# 03-CORE_BOARD.net
KiCad netlist of a schematic drawn in Altium Designer
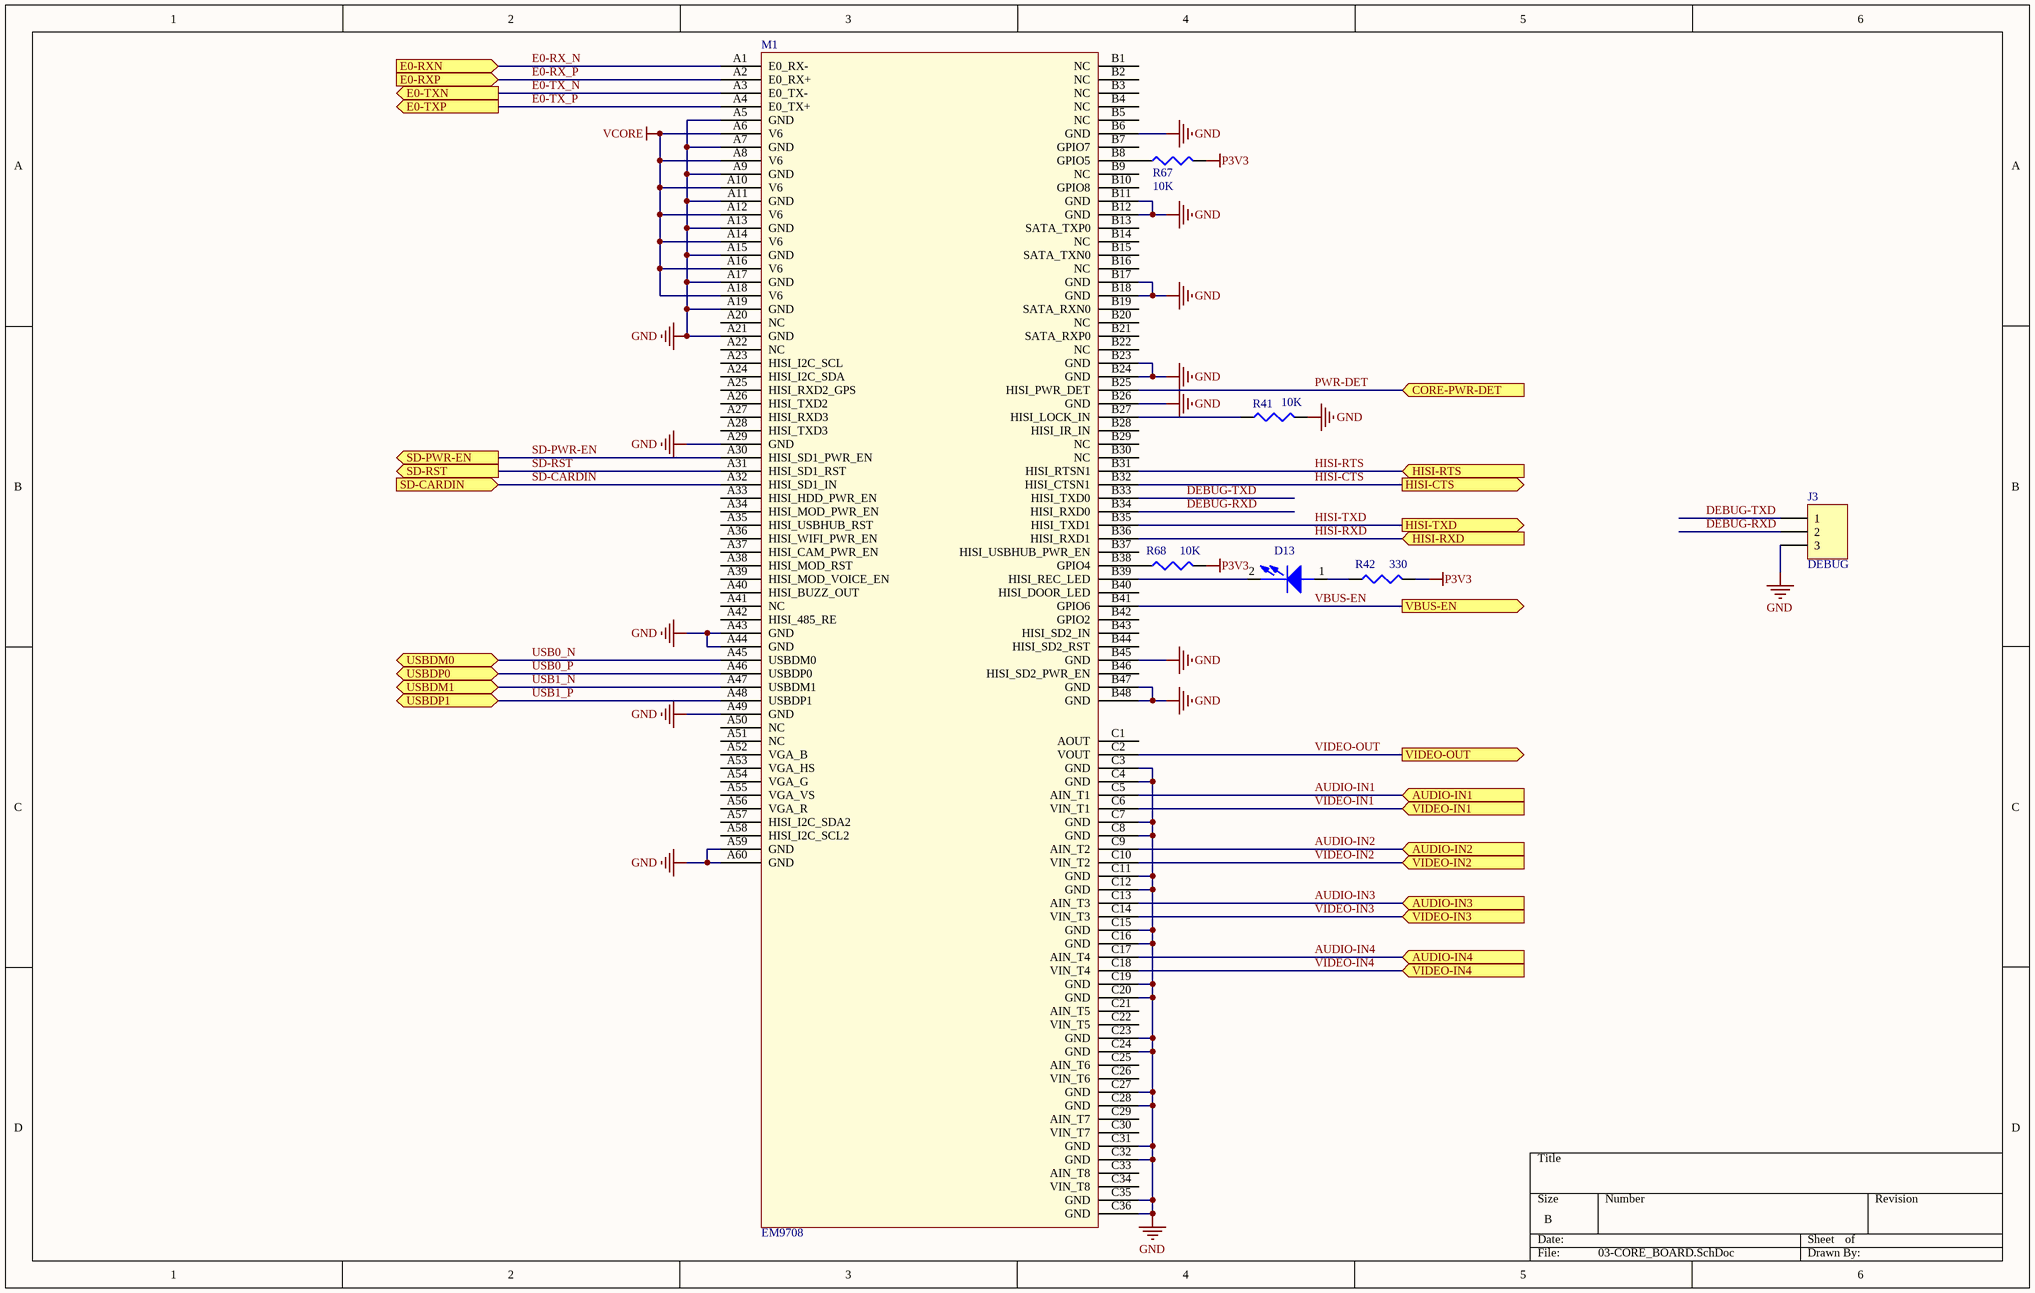
[diagram p0: 03-CORE_BOARD.SchDoc]

(export (version "E")
  (design (tool "Eeschema 10.0.6"))
  (components
    (comp (ref "D13") (value "LED GREEN") (footprint "LED0603") (libsource (lib "*") (part "LN01401_1")))
    (comp (ref "J3")
      (value "DEBUG")
      (footprint "HDR1X3")
      (description "Header, 3-Pin")
      (fields (field (name "PUBLISHER") "Altium Limited"))
      (libsource (lib "Miscellaneous Connectors") (part "Header 3"))
    )
    (comp (ref "M1") (value "EM9708") (footprint "EM9708") (libsource (lib "Schlib") (part "EM9708")))
    (comp (ref "R41")
      (value "10K")
      (footprint "0402")
      (description "Resistor")
      (fields (field (name "PUBLISHER") "Altium Limited"))
      (libsource (lib "Miscellaneous Devices") (part "Res3"))
    )
    (comp (ref "R42") (value "330") (footprint "0402") (libsource (lib "*") (part "CR16-1003FM")))
    (comp (ref "R67")
      (value "10K")
      (footprint "0402")
      (description "Resistor")
      (fields (field (name "PUBLISHER") "Altium Limited"))
      (libsource (lib "Miscellaneous Devices") (part "Res3"))
    )
    (comp (ref "R68")
      (value "10K")
      (footprint "0402")
      (description "Resistor")
      (fields (field (name "PUBLISHER") "Altium Limited"))
      (libsource (lib "Miscellaneous Devices") (part "Res3"))
    )
  )
  (nets
    (net (code "1") (name "/AUDIO-IN1") (class "Default")
      (node (ref "M1") (pin "C5") (pinfunction "AIN_T1_C5") (pintype "passive"))
    )
    (net (code "2") (name "/AUDIO-IN2") (class "Default")
      (node (ref "M1") (pin "C9") (pinfunction "AIN_T2_C9") (pintype "passive"))
    )
    (net (code "3") (name "/AUDIO-IN3") (class "Default")
      (node (ref "M1") (pin "C13") (pinfunction "AIN_T3_C13") (pintype "passive"))
    )
    (net (code "4") (name "/AUDIO-IN4") (class "Default")
      (node (ref "M1") (pin "C17") (pinfunction "AIN_T4_C17") (pintype "passive"))
    )
    (net (code "5") (name "/DEBUG-RXD") (class "Default")
      (node (ref "J3") (pin "2") (pinfunction "2_2") (pintype "passive"))
      (node (ref "M1") (pin "B34") (pinfunction "HISI_RXD0_B34") (pintype "passive"))
    )
    (net (code "6") (name "/DEBUG-TXD") (class "Default")
      (node (ref "J3") (pin "1") (pinfunction "1_1") (pintype "passive"))
      (node (ref "M1") (pin "B33") (pinfunction "HISI_TXD0_B33") (pintype "passive"))
    )
    (net (code "7") (name "/E0-RX_N") (class "Default")
      (node (ref "M1") (pin "A1") (pinfunction "E0_RX-_A1") (pintype "passive"))
    )
    (net (code "8") (name "/E0-RX_P") (class "Default")
      (node (ref "M1") (pin "A2") (pinfunction "E0_RX+_A2") (pintype "passive"))
    )
    (net (code "9") (name "/E0-TX_N") (class "Default")
      (node (ref "M1") (pin "A3") (pinfunction "E0_TX-_A3") (pintype "passive"))
    )
    (net (code "10") (name "/E0-TX_P") (class "Default")
      (node (ref "M1") (pin "A4") (pinfunction "E0_TX+_A4") (pintype "passive"))
    )
    (net (code "11") (name "/HISI-CTS") (class "Default")
      (node (ref "M1") (pin "B32") (pinfunction "HISI_CTSN1_B32") (pintype "passive"))
    )
    (net (code "12") (name "/HISI-RTS") (class "Default")
      (node (ref "M1") (pin "B31") (pinfunction "HISI_RTSN1_B31") (pintype "passive"))
    )
    (net (code "13") (name "/HISI-RXD") (class "Default")
      (node (ref "M1") (pin "B36") (pinfunction "HISI_RXD1_B36") (pintype "passive"))
    )
    (net (code "14") (name "/HISI-TXD") (class "Default")
      (node (ref "M1") (pin "B35") (pinfunction "HISI_TXD1_B35") (pintype "passive"))
    )
    (net (code "15") (name "/PWR-DET") (class "Default")
      (node (ref "M1") (pin "B25") (pinfunction "HISI_PWR_DET_B25") (pintype "passive"))
    )
    (net (code "16") (name "/SD-CARDIN") (class "Default")
      (node (ref "M1") (pin "A32") (pinfunction "HISI_SD1_IN_A32") (pintype "passive"))
    )
    (net (code "17") (name "/SD-PWR-EN") (class "Default")
      (node (ref "M1") (pin "A30") (pinfunction "HISI_SD1_PWR_EN_A30") (pintype "passive"))
    )
    (net (code "18") (name "/SD-RST") (class "Default")
      (node (ref "M1") (pin "A31") (pinfunction "HISI_SD1_RST_A31") (pintype "passive"))
    )
    (net (code "19") (name "/USB0_N") (class "Default")
      (node (ref "M1") (pin "A45") (pinfunction "USBDM0_A45") (pintype "passive"))
    )
    (net (code "20") (name "/USB0_P") (class "Default")
      (node (ref "M1") (pin "A46") (pinfunction "USBDP0_A46") (pintype "passive"))
    )
    (net (code "21") (name "/USB1_N") (class "Default")
      (node (ref "M1") (pin "A47") (pinfunction "USBDM1_A47") (pintype "passive"))
    )
    (net (code "22") (name "/USB1_P") (class "Default")
      (node (ref "M1") (pin "A48") (pinfunction "USBDP1_A48") (pintype "passive"))
    )
    (net (code "23") (name "/VBUS-EN") (class "Default")
      (node (ref "M1") (pin "B41") (pinfunction "GPIO6_B41") (pintype "passive"))
    )
    (net (code "24") (name "/VIDEO-IN1") (class "Default")
      (node (ref "M1") (pin "C6") (pinfunction "VIN_T1_C6") (pintype "passive"))
    )
    (net (code "25") (name "/VIDEO-IN2") (class "Default")
      (node (ref "M1") (pin "C10") (pinfunction "VIN_T2_C10") (pintype "passive"))
    )
    (net (code "26") (name "/VIDEO-IN3") (class "Default")
      (node (ref "M1") (pin "C14") (pinfunction "VIN_T3_C14") (pintype "passive"))
    )
    (net (code "27") (name "/VIDEO-IN4") (class "Default")
      (node (ref "M1") (pin "C18") (pinfunction "VIN_T4_C18") (pintype "passive"))
    )
    (net (code "28") (name "/VIDEO-OUT") (class "Default")
      (node (ref "M1") (pin "C2") (pinfunction "VOUT_C2") (pintype "passive"))
    )
    (net (code "29") (name "GND") (class "Default")
      (node (ref "J3") (pin "3") (pinfunction "3_3") (pintype "passive"))
      (node (ref "M1") (pin "A11") (pinfunction "GND_A11") (pintype "passive"))
      (node (ref "M1") (pin "A13") (pinfunction "GND_A13") (pintype "passive"))
      (node (ref "M1") (pin "A15") (pinfunction "GND_A15") (pintype "passive"))
      (node (ref "M1") (pin "A17") (pinfunction "GND_A17") (pintype "passive"))
      (node (ref "M1") (pin "A19") (pinfunction "GND_A19") (pintype "passive"))
      (node (ref "M1") (pin "A21") (pinfunction "GND_A21") (pintype "passive"))
      (node (ref "M1") (pin "A29") (pinfunction "GND_A29") (pintype "passive"))
      (node (ref "M1") (pin "A43") (pinfunction "GND_A43") (pintype "passive"))
      (node (ref "M1") (pin "A44") (pinfunction "GND_A44") (pintype "passive"))
      (node (ref "M1") (pin "A49") (pinfunction "GND_A49") (pintype "passive"))
      (node (ref "M1") (pin "A5") (pinfunction "GND_A5") (pintype "passive"))
      (node (ref "M1") (pin "A59") (pinfunction "GND_A59") (pintype "passive"))
      (node (ref "M1") (pin "A60") (pinfunction "GND_A60") (pintype "passive"))
      (node (ref "M1") (pin "A7") (pinfunction "GND_A7") (pintype "passive"))
      (node (ref "M1") (pin "A9") (pinfunction "GND_A9") (pintype "passive"))
      (node (ref "M1") (pin "B11") (pinfunction "GND_B11") (pintype "passive"))
      (node (ref "M1") (pin "B12") (pinfunction "GND_B12") (pintype "passive"))
      (node (ref "M1") (pin "B17") (pinfunction "GND_B17") (pintype "passive"))
      (node (ref "M1") (pin "B18") (pinfunction "GND_B18") (pintype "passive"))
      (node (ref "M1") (pin "B23") (pinfunction "GND_B23") (pintype "passive"))
      (node (ref "M1") (pin "B24") (pinfunction "GND_B24") (pintype "passive"))
      (node (ref "M1") (pin "B26") (pinfunction "GND_B26") (pintype "passive"))
      (node (ref "M1") (pin "B45") (pinfunction "GND_B45") (pintype "passive"))
      (node (ref "M1") (pin "B47") (pinfunction "GND_B47") (pintype "passive"))
      (node (ref "M1") (pin "B48") (pinfunction "GND_B48") (pintype "passive"))
      (node (ref "M1") (pin "B6") (pinfunction "GND_B6") (pintype "passive"))
      (node (ref "M1") (pin "C11") (pinfunction "GND_C11") (pintype "passive"))
      (node (ref "M1") (pin "C12") (pinfunction "GND_C12") (pintype "passive"))
      (node (ref "M1") (pin "C15") (pinfunction "GND_C15") (pintype "passive"))
      (node (ref "M1") (pin "C16") (pinfunction "GND_C16") (pintype "passive"))
      (node (ref "M1") (pin "C19") (pinfunction "GND_C19") (pintype "passive"))
      (node (ref "M1") (pin "C20") (pinfunction "GND_C20") (pintype "passive"))
      (node (ref "M1") (pin "C23") (pinfunction "GND_C23") (pintype "passive"))
      (node (ref "M1") (pin "C24") (pinfunction "GND_C24") (pintype "passive"))
      (node (ref "M1") (pin "C27") (pinfunction "GND_C27") (pintype "passive"))
      (node (ref "M1") (pin "C28") (pinfunction "GND_C28") (pintype "passive"))
      (node (ref "M1") (pin "C3") (pinfunction "GND_C3") (pintype "passive"))
      (node (ref "M1") (pin "C31") (pinfunction "GND_C31") (pintype "passive"))
      (node (ref "M1") (pin "C32") (pinfunction "GND_C32") (pintype "passive"))
      (node (ref "M1") (pin "C35") (pinfunction "GND_C35") (pintype "passive"))
      (node (ref "M1") (pin "C36") (pinfunction "GND_C36") (pintype "passive"))
      (node (ref "M1") (pin "C4") (pinfunction "GND_C4") (pintype "passive"))
      (node (ref "M1") (pin "C7") (pinfunction "GND_C7") (pintype "passive"))
      (node (ref "M1") (pin "C8") (pinfunction "GND_C8") (pintype "passive"))
      (node (ref "R41") (pin "2") (pinfunction "2_2") (pintype "passive"))
    )
    (net (code "30") (name "Net-(D13-ANODE)") (class "Default")
      (node (ref "D13") (pin "1") (pinfunction "ANODE_1") (pintype "passive"))
      (node (ref "R42") (pin "2") (pinfunction "2_2") (pintype "passive"))
    )
    (net (code "31") (name "Net-(D13-CATHODE)") (class "Default")
      (node (ref "D13") (pin "2") (pinfunction "CATHODE_2") (pintype "passive"))
      (node (ref "M1") (pin "B39") (pinfunction "HISI_REC_LED_B39") (pintype "passive"))
    )
    (net (code "32") (name "Net-(M1-GPIO4)") (class "Default")
      (node (ref "M1") (pin "B38") (pinfunction "GPIO4_B38") (pintype "passive"))
      (node (ref "R68") (pin "1") (pinfunction "1_1") (pintype "passive"))
    )
    (net (code "33") (name "Net-(M1-GPIO5)") (class "Default")
      (node (ref "M1") (pin "B8") (pinfunction "GPIO5_B8") (pintype "passive"))
      (node (ref "R67") (pin "1") (pinfunction "1_1") (pintype "passive"))
    )
    (net (code "34") (name "Net-(M1-HISI_LOCK_IN)") (class "Default")
      (node (ref "M1") (pin "B27") (pinfunction "HISI_LOCK_IN_B27") (pintype "passive"))
      (node (ref "R41") (pin "1") (pinfunction "1_1") (pintype "passive"))
    )
    (net (code "35") (name "P3V3") (class "Default")
      (node (ref "R42") (pin "1") (pinfunction "1_1") (pintype "passive"))
      (node (ref "R67") (pin "2") (pinfunction "2_2") (pintype "passive"))
      (node (ref "R68") (pin "2") (pinfunction "2_2") (pintype "passive"))
    )
    (net (code "36") (name "VCORE") (class "Default")
      (node (ref "M1") (pin "A10") (pinfunction "V6_A10") (pintype "passive"))
      (node (ref "M1") (pin "A12") (pinfunction "V6_A12") (pintype "passive"))
      (node (ref "M1") (pin "A14") (pinfunction "V6_A14") (pintype "passive"))
      (node (ref "M1") (pin "A16") (pinfunction "V6_A16") (pintype "passive"))
      (node (ref "M1") (pin "A18") (pinfunction "V6_A18") (pintype "passive"))
      (node (ref "M1") (pin "A6") (pinfunction "V6_A6") (pintype "passive"))
      (node (ref "M1") (pin "A8") (pinfunction "V6_A8") (pintype "passive"))
    )
    (net (code "37") (name "unconnected-(M1-AIN_T5-PadC21)") (class "Default")
      (node (ref "M1") (pin "C21") (pinfunction "AIN_T5_C21") (pintype "passive"))
    )
    (net (code "38") (name "unconnected-(M1-AIN_T6-PadC25)") (class "Default")
      (node (ref "M1") (pin "C25") (pinfunction "AIN_T6_C25") (pintype "passive"))
    )
    (net (code "39") (name "unconnected-(M1-AIN_T7-PadC29)") (class "Default")
      (node (ref "M1") (pin "C29") (pinfunction "AIN_T7_C29") (pintype "passive"))
    )
    (net (code "40") (name "unconnected-(M1-AIN_T8-PadC33)") (class "Default")
      (node (ref "M1") (pin "C33") (pinfunction "AIN_T8_C33") (pintype "passive"))
    )
    (net (code "41") (name "unconnected-(M1-AOUT-PadC1)") (class "Default")
      (node (ref "M1") (pin "C1") (pinfunction "AOUT_C1") (pintype "passive"))
    )
    (net (code "42") (name "unconnected-(M1-GPIO2-PadB42)") (class "Default")
      (node (ref "M1") (pin "B42") (pinfunction "GPIO2_B42") (pintype "passive"))
    )
    (net (code "43") (name "unconnected-(M1-GPIO7-PadB7)") (class "Default")
      (node (ref "M1") (pin "B7") (pinfunction "GPIO7_B7") (pintype "passive"))
    )
    (net (code "44") (name "unconnected-(M1-GPIO8-PadB10)") (class "Default")
      (node (ref "M1") (pin "B10") (pinfunction "GPIO8_B10") (pintype "passive"))
    )
    (net (code "45") (name "unconnected-(M1-HISI_485_RE-PadA42)") (class "Default")
      (node (ref "M1") (pin "A42") (pinfunction "HISI_485_RE_A42") (pintype "passive"))
    )
    (net (code "46") (name "unconnected-(M1-HISI_BUZZ_OUT-PadA40)") (class "Default")
      (node (ref "M1") (pin "A40") (pinfunction "HISI_BUZZ_OUT_A40") (pintype "passive"))
    )
    (net (code "47") (name "unconnected-(M1-HISI_CAM_PWR_EN-PadA37)") (class "Default")
      (node (ref "M1") (pin "A37") (pinfunction "HISI_CAM_PWR_EN_A37") (pintype "passive"))
    )
    (net (code "48") (name "unconnected-(M1-HISI_DOOR_LED-PadB40)") (class "Default")
      (node (ref "M1") (pin "B40") (pinfunction "HISI_DOOR_LED_B40") (pintype "passive"))
    )
    (net (code "49") (name "unconnected-(M1-HISI_HDD_PWR_EN-PadA33)") (class "Default")
      (node (ref "M1") (pin "A33") (pinfunction "HISI_HDD_PWR_EN_A33") (pintype "passive"))
    )
    (net (code "50") (name "unconnected-(M1-HISI_I2C_SCL-PadA23)") (class "Default")
      (node (ref "M1") (pin "A23") (pinfunction "HISI_I2C_SCL_A23") (pintype "passive"))
    )
    (net (code "51") (name "unconnected-(M1-HISI_I2C_SCL2-PadA58)") (class "Default")
      (node (ref "M1") (pin "A58") (pinfunction "HISI_I2C_SCL2_A58") (pintype "passive"))
    )
    (net (code "52") (name "unconnected-(M1-HISI_I2C_SDA-PadA24)") (class "Default")
      (node (ref "M1") (pin "A24") (pinfunction "HISI_I2C_SDA_A24") (pintype "passive"))
    )
    (net (code "53") (name "unconnected-(M1-HISI_I2C_SDA2-PadA57)") (class "Default")
      (node (ref "M1") (pin "A57") (pinfunction "HISI_I2C_SDA2_A57") (pintype "passive"))
    )
    (net (code "54") (name "unconnected-(M1-HISI_IR_IN-PadB28)") (class "Default")
      (node (ref "M1") (pin "B28") (pinfunction "HISI_IR_IN_B28") (pintype "passive"))
    )
    (net (code "55") (name "unconnected-(M1-HISI_MOD_PWR_EN-PadA34)") (class "Default")
      (node (ref "M1") (pin "A34") (pinfunction "HISI_MOD_PWR_EN_A34") (pintype "passive"))
    )
    (net (code "56") (name "unconnected-(M1-HISI_MOD_RST-PadA38)") (class "Default")
      (node (ref "M1") (pin "A38") (pinfunction "HISI_MOD_RST_A38") (pintype "passive"))
    )
    (net (code "57") (name "unconnected-(M1-HISI_MOD_VOICE_EN-PadA39)") (class "Default")
      (node (ref "M1") (pin "A39") (pinfunction "HISI_MOD_VOICE_EN_A39") (pintype "passive"))
    )
    (net (code "58") (name "unconnected-(M1-HISI_RXD2_GPS-PadA25)") (class "Default")
      (node (ref "M1") (pin "A25") (pinfunction "HISI_RXD2_GPS_A25") (pintype "passive"))
    )
    (net (code "59") (name "unconnected-(M1-HISI_RXD3-PadA27)") (class "Default")
      (node (ref "M1") (pin "A27") (pinfunction "HISI_RXD3_A27") (pintype "passive"))
    )
    (net (code "60") (name "unconnected-(M1-HISI_SD2_IN-PadB43)") (class "Default")
      (node (ref "M1") (pin "B43") (pinfunction "HISI_SD2_IN_B43") (pintype "passive"))
    )
    (net (code "61") (name "unconnected-(M1-HISI_SD2_PWR_EN-PadB46)") (class "Default")
      (node (ref "M1") (pin "B46") (pinfunction "HISI_SD2_PWR_EN_B46") (pintype "passive"))
    )
    (net (code "62") (name "unconnected-(M1-HISI_SD2_RST-PadB44)") (class "Default")
      (node (ref "M1") (pin "B44") (pinfunction "HISI_SD2_RST_B44") (pintype "passive"))
    )
    (net (code "63") (name "unconnected-(M1-HISI_TXD2-PadA26)") (class "Default")
      (node (ref "M1") (pin "A26") (pinfunction "HISI_TXD2_A26") (pintype "passive"))
    )
    (net (code "64") (name "unconnected-(M1-HISI_TXD3-PadA28)") (class "Default")
      (node (ref "M1") (pin "A28") (pinfunction "HISI_TXD3_A28") (pintype "passive"))
    )
    (net (code "65") (name "unconnected-(M1-HISI_USBHUB_PWR_EN-PadB37)") (class "Default")
      (node (ref "M1") (pin "B37") (pinfunction "HISI_USBHUB_PWR_EN_B37") (pintype "passive"))
    )
    (net (code "66") (name "unconnected-(M1-HISI_USBHUB_RST-PadA35)") (class "Default")
      (node (ref "M1") (pin "A35") (pinfunction "HISI_USBHUB_RST_A35") (pintype "passive"))
    )
    (net (code "67") (name "unconnected-(M1-HISI_WIFI_PWR_EN-PadA36)") (class "Default")
      (node (ref "M1") (pin "A36") (pinfunction "HISI_WIFI_PWR_EN_A36") (pintype "passive"))
    )
    (net (code "68") (name "unconnected-(M1-NC-PadA20)") (class "Default")
      (node (ref "M1") (pin "A20") (pinfunction "NC_A20") (pintype "passive"))
    )
    (net (code "69") (name "unconnected-(M1-NC-PadA22)") (class "Default")
      (node (ref "M1") (pin "A22") (pinfunction "NC_A22") (pintype "passive"))
    )
    (net (code "70") (name "unconnected-(M1-NC-PadA41)") (class "Default")
      (node (ref "M1") (pin "A41") (pinfunction "NC_A41") (pintype "passive"))
    )
    (net (code "71") (name "unconnected-(M1-NC-PadA50)") (class "Default")
      (node (ref "M1") (pin "A50") (pinfunction "NC_A50") (pintype "passive"))
    )
    (net (code "72") (name "unconnected-(M1-NC-PadA51)") (class "Default")
      (node (ref "M1") (pin "A51") (pinfunction "NC_A51") (pintype "passive"))
    )
    (net (code "73") (name "unconnected-(M1-NC-PadB1)") (class "Default")
      (node (ref "M1") (pin "B1") (pinfunction "NC_B1") (pintype "passive"))
    )
    (net (code "74") (name "unconnected-(M1-NC-PadB2)") (class "Default")
      (node (ref "M1") (pin "B2") (pinfunction "NC_B2") (pintype "passive"))
    )
    (net (code "75") (name "unconnected-(M1-NC-PadB3)") (class "Default")
      (node (ref "M1") (pin "B3") (pinfunction "NC_B3") (pintype "passive"))
    )
    (net (code "76") (name "unconnected-(M1-NC-PadB4)") (class "Default")
      (node (ref "M1") (pin "B4") (pinfunction "NC_B4") (pintype "passive"))
    )
    (net (code "77") (name "unconnected-(M1-NC-PadB5)") (class "Default")
      (node (ref "M1") (pin "B5") (pinfunction "NC_B5") (pintype "passive"))
    )
    (net (code "78") (name "unconnected-(M1-NC-PadB9)") (class "Default")
      (node (ref "M1") (pin "B9") (pinfunction "NC_B9") (pintype "passive"))
    )
    (net (code "79") (name "unconnected-(M1-NC-PadB14)") (class "Default")
      (node (ref "M1") (pin "B14") (pinfunction "NC_B14") (pintype "passive"))
    )
    (net (code "80") (name "unconnected-(M1-NC-PadB16)") (class "Default")
      (node (ref "M1") (pin "B16") (pinfunction "NC_B16") (pintype "passive"))
    )
    (net (code "81") (name "unconnected-(M1-NC-PadB20)") (class "Default")
      (node (ref "M1") (pin "B20") (pinfunction "NC_B20") (pintype "passive"))
    )
    (net (code "82") (name "unconnected-(M1-NC-PadB22)") (class "Default")
      (node (ref "M1") (pin "B22") (pinfunction "NC_B22") (pintype "passive"))
    )
    (net (code "83") (name "unconnected-(M1-NC-PadB29)") (class "Default")
      (node (ref "M1") (pin "B29") (pinfunction "NC_B29") (pintype "passive"))
    )
    (net (code "84") (name "unconnected-(M1-NC-PadB30)") (class "Default")
      (node (ref "M1") (pin "B30") (pinfunction "NC_B30") (pintype "passive"))
    )
    (net (code "85") (name "unconnected-(M1-SATA_RXN0-PadB19)") (class "Default")
      (node (ref "M1") (pin "B19") (pinfunction "SATA_RXN0_B19") (pintype "passive"))
    )
    (net (code "86") (name "unconnected-(M1-SATA_RXP0-PadB21)") (class "Default")
      (node (ref "M1") (pin "B21") (pinfunction "SATA_RXP0_B21") (pintype "passive"))
    )
    (net (code "87") (name "unconnected-(M1-SATA_TXN0-PadB15)") (class "Default")
      (node (ref "M1") (pin "B15") (pinfunction "SATA_TXN0_B15") (pintype "passive"))
    )
    (net (code "88") (name "unconnected-(M1-SATA_TXP0-PadB13)") (class "Default")
      (node (ref "M1") (pin "B13") (pinfunction "SATA_TXP0_B13") (pintype "passive"))
    )
    (net (code "89") (name "unconnected-(M1-VGA_B-PadA52)") (class "Default")
      (node (ref "M1") (pin "A52") (pinfunction "VGA_B_A52") (pintype "passive"))
    )
    (net (code "90") (name "unconnected-(M1-VGA_G-PadA54)") (class "Default")
      (node (ref "M1") (pin "A54") (pinfunction "VGA_G_A54") (pintype "passive"))
    )
    (net (code "91") (name "unconnected-(M1-VGA_HS-PadA53)") (class "Default")
      (node (ref "M1") (pin "A53") (pinfunction "VGA_HS_A53") (pintype "passive"))
    )
    (net (code "92") (name "unconnected-(M1-VGA_R-PadA56)") (class "Default")
      (node (ref "M1") (pin "A56") (pinfunction "VGA_R_A56") (pintype "passive"))
    )
    (net (code "93") (name "unconnected-(M1-VGA_VS-PadA55)") (class "Default")
      (node (ref "M1") (pin "A55") (pinfunction "VGA_VS_A55") (pintype "passive"))
    )
    (net (code "94") (name "unconnected-(M1-VIN_T5-PadC22)") (class "Default")
      (node (ref "M1") (pin "C22") (pinfunction "VIN_T5_C22") (pintype "passive"))
    )
    (net (code "95") (name "unconnected-(M1-VIN_T6-PadC26)") (class "Default")
      (node (ref "M1") (pin "C26") (pinfunction "VIN_T6_C26") (pintype "passive"))
    )
    (net (code "96") (name "unconnected-(M1-VIN_T7-PadC30)") (class "Default")
      (node (ref "M1") (pin "C30") (pinfunction "VIN_T7_C30") (pintype "passive"))
    )
    (net (code "97") (name "unconnected-(M1-VIN_T8-PadC34)") (class "Default")
      (node (ref "M1") (pin "C34") (pinfunction "VIN_T8_C34") (pintype "passive"))
    )
  )
)
